# ga_panel.net
KiCad netlist of a schematic drawn in EAGLE
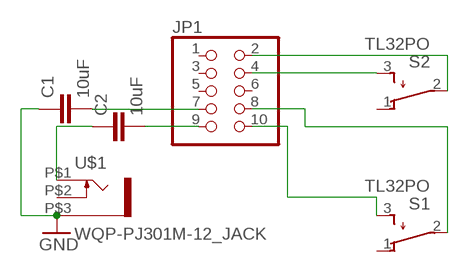
[diagram p0: schematic, sheet 1]

(export (version "E")
  (design (tool "Eeschema 10.0.6"))
  (components
    (comp (ref "C1")
      (value "10uF")
      (footprint "eagle-import:C5B3.5")
      (libsource (lib "eagle-import") (part "C5/3.5"))
    )
    (comp (ref "C2")
      (value "10uF")
      (footprint "eagle-import:C5B3.5")
      (libsource (lib "eagle-import") (part "C5/3.5"))
    )
    (comp (ref "JP1")
      (value "PINHD-2X5")
      (footprint "eagle-import:2X05")
      (libsource (lib "eagle-import") (part "PINHD-2X5"))
    )
    (comp (ref "S1")
      (value "TL32PO")
      (footprint "eagle-import:TL3XPO")
      (libsource (lib "eagle-import") (part "TL32PO"))
    )
    (comp (ref "S2")
      (value "TL32PO")
      (footprint "eagle-import:TL3XPO")
      (libsource (lib "eagle-import") (part "TL32PO"))
    )
    (comp (ref "U$1")
      (value "WQP-PJ301M-12_JACK")
      (footprint "eagle-import:WQP-PJ301M-12_JACK")
      (libsource (lib "eagle-import") (part "WQP-PJ301M-12_JACK"))
    )
  )
  (nets
    (net (code "1") (name "GND") (class "Default")
      (node (ref "C1") (pin "1") (pinfunction "1_1") (pintype "passive"))
      (node (ref "U$1") (pin "P$3") (pinfunction "1_P$3") (pintype "passive"))
    )
    (net (code "2") (name "Net-(C1-Pad2)") (class "Default")
      (node (ref "C1") (pin "2") (pinfunction "2_2") (pintype "passive"))
      (node (ref "JP1") (pin "7") (pinfunction "7_7") (pintype "passive"))
    )
    (net (code "3") (name "Net-(C2-Pad2)") (class "Default")
      (node (ref "C2") (pin "2") (pinfunction "2_2") (pintype "passive"))
      (node (ref "JP1") (pin "9") (pinfunction "9_9") (pintype "passive"))
    )
    (net (code "4") (name "Net-(S1-P)") (class "Default")
      (node (ref "JP1") (pin "8") (pinfunction "8_8") (pintype "passive"))
      (node (ref "S1") (pin "2") (pinfunction "P_2") (pintype "passive"))
    )
    (net (code "5") (name "Net-(S1-S)") (class "Default")
      (node (ref "JP1") (pin "10") (pinfunction "10_10") (pintype "passive"))
      (node (ref "S1") (pin "3") (pinfunction "S_3") (pintype "passive"))
    )
    (net (code "6") (name "Net-(S2-P)") (class "Default")
      (node (ref "JP1") (pin "2") (pinfunction "2_2") (pintype "passive"))
      (node (ref "S2") (pin "2") (pinfunction "P_2") (pintype "passive"))
    )
    (net (code "7") (name "Net-(S2-S)") (class "Default")
      (node (ref "JP1") (pin "4") (pinfunction "4_4") (pintype "passive"))
      (node (ref "S2") (pin "3") (pinfunction "S_3") (pintype "passive"))
    )
    (net (code "8") (name "Net-(U$1-2)") (class "Default")
      (node (ref "C2") (pin "1") (pinfunction "1_1") (pintype "passive"))
      (node (ref "U$1") (pin "P$1") (pinfunction "2_P$1") (pintype "passive"))
    )
    (net (code "9") (name "unconnected-(JP1-Pad1)") (class "Default")
      (node (ref "JP1") (pin "1") (pinfunction "1_1") (pintype "passive"))
    )
    (net (code "10") (name "unconnected-(JP1-Pad3)") (class "Default")
      (node (ref "JP1") (pin "3") (pinfunction "3_3") (pintype "passive"))
    )
    (net (code "11") (name "unconnected-(JP1-Pad5)") (class "Default")
      (node (ref "JP1") (pin "5") (pinfunction "5_5") (pintype "passive"))
    )
    (net (code "12") (name "unconnected-(JP1-Pad6)") (class "Default")
      (node (ref "JP1") (pin "6") (pinfunction "6_6") (pintype "passive"))
    )
    (net (code "13") (name "unconnected-(S1-O-Pad1)") (class "Default")
      (node (ref "S1") (pin "1") (pinfunction "O_1") (pintype "passive"))
    )
    (net (code "14") (name "unconnected-(S2-O-Pad1)") (class "Default")
      (node (ref "S2") (pin "1") (pinfunction "O_1") (pintype "passive"))
    )
    (net (code "15") (name "unconnected-(U$1-3-PadP$2)") (class "Default")
      (node (ref "U$1") (pin "P$2") (pinfunction "3_P$2") (pintype "passive"))
    )
  )
)
